# RJ45.net
KiCad netlist of a schematic drawn in Altium Designer
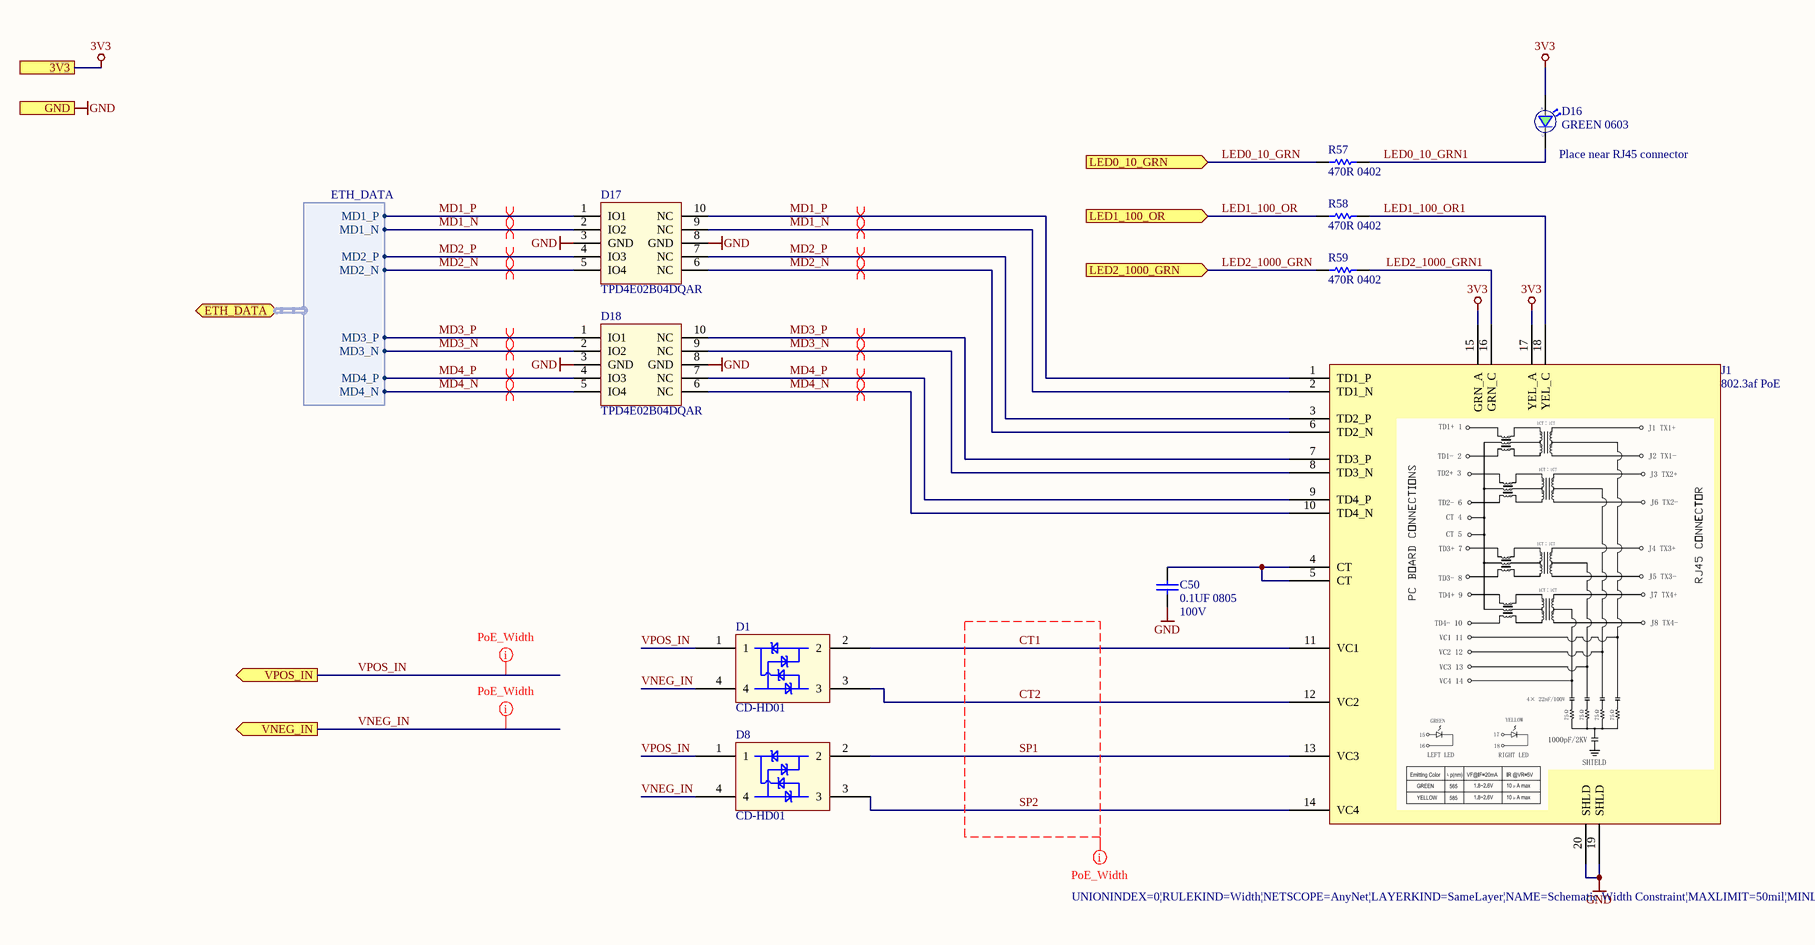
[diagram p0: RJ45.SchDoc]

(export (version "E")
  (design (tool "Eeschema 10.0.6"))
  (components
    (comp (ref "C50")
      (value "0.1UF 0805")
      (footprint "CAP_Altium_Vault_Generic:CAPC0805(2012)145_N")
      (description "CAP CER 0.1UF 100V X7R 0805")
      (fields (field (name "TOLERANCE") "10%") (field (name "VOLTAGE RATING") "100V"))
      (libsource (lib "PCBProject") (part "CL21B104KCFNNNE"))
    )
    (comp (ref "D1")
      (value "CD-HD01")
      (footprint "CD-H01")
      (description "CD-HD0x Series Schottky Bridge Rectifier Diode 100V 4-Pin Surface Mount T/R")
      (libsource (lib "DM1097_R1M1E1") (part "CD-HD01"))
    )
    (comp (ref "D8")
      (value "CD-HD01")
      (footprint "CD-H01")
      (description "CD-HD0x Series Schottky Bridge Rectifier Diode 100V 4-Pin Surface Mount T/R")
      (libsource (lib "DM1097_R1M1E1") (part "CD-HD01"))
    )
    (comp (ref "D16")
      (value "GREEN 0603")
      (footprint "LuxonisMaster:SML_D1xx8W")
      (description "LED GREEN DIFFUSED 0603 SMD Green 572nm LED Indication - Discrete 2.2V 0603 (1608 Metric)")
      (fields (field (name "MANUFACTURER") "Rohm") (field (name "MANUFACTURER PART NUMBER") "SML-D12M8WT86"))
      (libsource (lib "LuxonisMaster") (part "SML-D12M8WT86"))
    )
    (comp (ref "D17")
      (value "TPD4E02B04DQAR")
      (footprint "LuxonisMaster:TPD4E02B04DQAR")
      (libsource (lib "LuxonisMaster") (part "TPD4E02B04DQAR"))
    )
    (comp (ref "D18")
      (value "TPD4E02B04DQAR")
      (footprint "LuxonisMaster:TPD4E02B04DQAR")
      (libsource (lib "LuxonisMaster") (part "TPD4E02B04DQAR"))
    )
    (comp (ref "J1")
      (value "802.3af PoE")
      (footprint "BW2098POE:TRJG0926HENL")
      (description "CONN MAGJACK 1PORT 1000 BASET")
      (libsource (lib "BW2098POE") (part "TRJG0926HENL"))
    )
    (comp (ref "R57")
      (value "470R 0402")
      (footprint "RES_Altium_Vault_Generic:RESC0402(1005)_N")
      (description "RES SMD 470 OHM 1% 1/16W 0402")
      (fields (field (name "TOLERANCE") "1%"))
      (libsource (lib "LuxonisMaster") (part "CRCW0402470RFKED"))
    )
    (comp (ref "R58")
      (value "470R 0402")
      (footprint "RES_Altium_Vault_Generic:RESC0402(1005)_N")
      (description "RES SMD 470 OHM 1% 1/16W 0402")
      (fields (field (name "TOLERANCE") "1%"))
      (libsource (lib "LuxonisMaster") (part "CRCW0402470RFKED"))
    )
    (comp (ref "R59")
      (value "470R 0402")
      (footprint "RES_Altium_Vault_Generic:RESC0402(1005)_N")
      (description "RES SMD 470 OHM 1% 1/16W 0402")
      (fields (field (name "TOLERANCE") "1%"))
      (libsource (lib "LuxonisMaster") (part "CRCW0402470RFKED"))
    )
  )
  (nets
    (net (code "2") (name "/CT1") (class "Default")
      (node (ref "D1") (pin "2") (pinfunction "2_2") (pintype "passive"))
      (node (ref "J1") (pin "11") (pinfunction "VC1_11") (pintype "passive"))
    )
    (net (code "3") (name "/CT2") (class "Default")
      (node (ref "D1") (pin "3") (pinfunction "3_3") (pintype "passive"))
      (node (ref "J1") (pin "12") (pinfunction "VC2_12") (pintype "passive"))
    )
    (net (code "4") (name "/LED0_10_GRN") (class "Default")
      (node (ref "R57") (pin "1") (pinfunction "1_1") (pintype "passive"))
    )
    (net (code "5") (name "/LED0_10_GRN1") (class "Default")
      (node (ref "D16") (pin "1") (pinfunction "C_1") (pintype "passive"))
      (node (ref "R57") (pin "2") (pinfunction "2_2") (pintype "passive"))
    )
    (net (code "6") (name "/LED1_100_OR") (class "Default")
      (node (ref "R58") (pin "1") (pinfunction "1_1") (pintype "passive"))
    )
    (net (code "7") (name "/LED1_100_OR1") (class "Default")
      (node (ref "J1") (pin "18") (pinfunction "YEL_C_18") (pintype "passive"))
      (node (ref "R58") (pin "2") (pinfunction "2_2") (pintype "passive"))
    )
    (net (code "8") (name "/LED2_1000_GRN") (class "Default")
      (node (ref "R59") (pin "1") (pinfunction "1_1") (pintype "passive"))
    )
    (net (code "9") (name "/LED2_1000_GRN1") (class "Default")
      (node (ref "J1") (pin "16") (pinfunction "GRN_C_16") (pintype "passive"))
      (node (ref "R59") (pin "2") (pinfunction "2_2") (pintype "passive"))
    )
    (net (code "10") (name "/MD1_N") (class "Default")
      (node (ref "D17") (pin "2") (pinfunction "IO2_2") (pintype "passive"))
      (node (ref "D17") (pin "9") (pinfunction "NC_9") (pintype "passive"))
      (node (ref "J1") (pin "2") (pinfunction "TD1_N_2") (pintype "passive"))
    )
    (net (code "11") (name "/MD1_P") (class "Default")
      (node (ref "D17") (pin "1") (pinfunction "IO1_1") (pintype "passive"))
      (node (ref "D17") (pin "10") (pinfunction "NC_10") (pintype "passive"))
      (node (ref "J1") (pin "1") (pinfunction "TD1_P_1") (pintype "passive"))
    )
    (net (code "12") (name "/MD2_N") (class "Default")
      (node (ref "D17") (pin "5") (pinfunction "IO4_5") (pintype "passive"))
      (node (ref "D17") (pin "6") (pinfunction "NC_6") (pintype "passive"))
      (node (ref "J1") (pin "6") (pinfunction "TD2_N_6") (pintype "passive"))
    )
    (net (code "13") (name "/MD2_P") (class "Default")
      (node (ref "D17") (pin "4") (pinfunction "IO3_4") (pintype "passive"))
      (node (ref "D17") (pin "7") (pinfunction "NC_7") (pintype "passive"))
      (node (ref "J1") (pin "3") (pinfunction "TD2_P_3") (pintype "passive"))
    )
    (net (code "14") (name "/MD3_N") (class "Default")
      (node (ref "D18") (pin "2") (pinfunction "IO2_2") (pintype "passive"))
      (node (ref "D18") (pin "9") (pinfunction "NC_9") (pintype "passive"))
      (node (ref "J1") (pin "8") (pinfunction "TD3_N_8") (pintype "passive"))
    )
    (net (code "15") (name "/MD3_P") (class "Default")
      (node (ref "D18") (pin "1") (pinfunction "IO1_1") (pintype "passive"))
      (node (ref "D18") (pin "10") (pinfunction "NC_10") (pintype "passive"))
      (node (ref "J1") (pin "7") (pinfunction "TD3_P_7") (pintype "passive"))
    )
    (net (code "16") (name "/MD4_N") (class "Default")
      (node (ref "D18") (pin "5") (pinfunction "IO4_5") (pintype "passive"))
      (node (ref "D18") (pin "6") (pinfunction "NC_6") (pintype "passive"))
      (node (ref "J1") (pin "10") (pinfunction "TD4_N_10") (pintype "passive"))
    )
    (net (code "17") (name "/MD4_P") (class "Default")
      (node (ref "D18") (pin "4") (pinfunction "IO3_4") (pintype "passive"))
      (node (ref "D18") (pin "7") (pinfunction "NC_7") (pintype "passive"))
      (node (ref "J1") (pin "9") (pinfunction "TD4_P_9") (pintype "passive"))
    )
    (net (code "18") (name "/SP1") (class "Default")
      (node (ref "D8") (pin "2") (pinfunction "2_2") (pintype "passive"))
      (node (ref "J1") (pin "13") (pinfunction "VC3_13") (pintype "passive"))
    )
    (net (code "19") (name "/SP2") (class "Default")
      (node (ref "D8") (pin "3") (pinfunction "3_3") (pintype "passive"))
      (node (ref "J1") (pin "14") (pinfunction "VC4_14") (pintype "passive"))
    )
    (net (code "20") (name "/VNEG_IN") (class "Default")
      (node (ref "D1") (pin "4") (pinfunction "4_4") (pintype "passive"))
      (node (ref "D8") (pin "4") (pinfunction "4_4") (pintype "passive"))
    )
    (net (code "21") (name "/VPOS_IN") (class "Default")
      (node (ref "D1") (pin "1") (pinfunction "1_1") (pintype "passive"))
      (node (ref "D8") (pin "1") (pinfunction "1_1") (pintype "passive"))
    )
    (net (code "23") (name "3V3") (class "Default")
      (node (ref "D16") (pin "2") (pinfunction "A_2") (pintype "passive"))
      (node (ref "J1") (pin "15") (pinfunction "GRN_A_15") (pintype "passive"))
      (node (ref "J1") (pin "17") (pinfunction "YEL_A_17") (pintype "passive"))
    )
    (net (code "24") (name "GND") (class "Default")
      (node (ref "C50") (pin "1") (pinfunction "1_1") (pintype "passive"))
      (node (ref "D17") (pin "3") (pinfunction "GND_3") (pintype "passive"))
      (node (ref "D17") (pin "8") (pinfunction "GND_8") (pintype "passive"))
      (node (ref "D18") (pin "3") (pinfunction "GND_3") (pintype "passive"))
      (node (ref "D18") (pin "8") (pinfunction "GND_8") (pintype "passive"))
      (node (ref "J1") (pin "19") (pinfunction "SHLD_19") (pintype "passive"))
      (node (ref "J1") (pin "20") (pinfunction "SHLD_20") (pintype "passive"))
    )
    (net (code "25") (name "Net-(C50-Pad2)") (class "Default")
      (node (ref "C50") (pin "2") (pinfunction "2_2") (pintype "passive"))
      (node (ref "J1") (pin "4") (pinfunction "CT_4") (pintype "passive"))
      (node (ref "J1") (pin "5") (pinfunction "CT_5") (pintype "passive"))
    )
  )
)
